# platine-crocodile.net
KiCad netlist of a schematic drawn in EAGLE
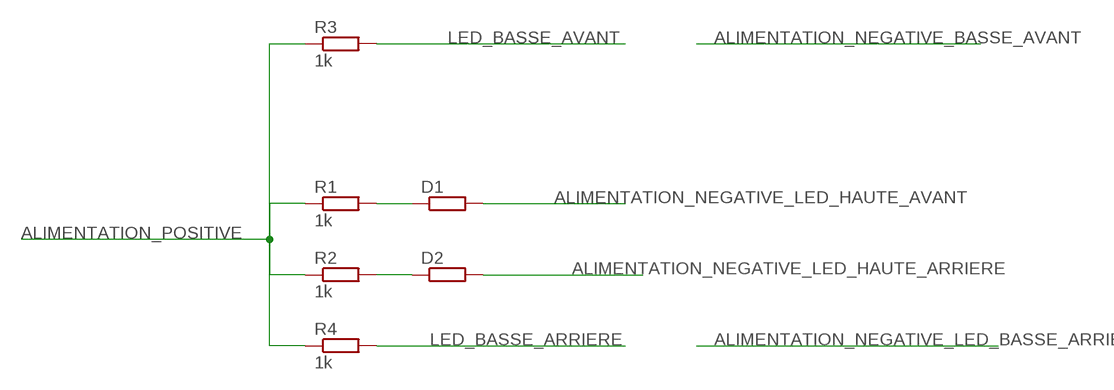
[diagram p0: schematic, sheet 1]

(export (version "E")
  (design (tool "Eeschema 10.0.6"))
  (components
    (comp (ref "D1")
      (value "R-EU_M0805")
      (footprint "eagle-import:M0805")
      (libsource (lib "eagle-import") (part "R-EU_M0805"))
    )
    (comp (ref "D2")
      (value "R-EU_M0805")
      (footprint "eagle-import:M0805")
      (libsource (lib "eagle-import") (part "R-EU_M0805"))
    )
    (comp (ref "R1")
      (value "1k")
      (footprint "eagle-import:M1206")
      (libsource (lib "eagle-import") (part "R-EU_M1206"))
    )
    (comp (ref "R2")
      (value "1k")
      (footprint "eagle-import:M1206")
      (libsource (lib "eagle-import") (part "R-EU_M1206"))
    )
    (comp (ref "R3")
      (value "1k")
      (footprint "eagle-import:M1206")
      (libsource (lib "eagle-import") (part "R-EU_M1206"))
    )
    (comp (ref "R4")
      (value "1k")
      (footprint "eagle-import:M1206")
      (libsource (lib "eagle-import") (part "R-EU_M1206"))
    )
  )
  (nets
    (net (code "3") (name "/ALIMENTATION_NEGATIVE_LED_HAUTE_ARRIERE") (class "Default")
      (node (ref "D2") (pin "2") (pinfunction "2_2") (pintype "passive"))
    )
    (net (code "4") (name "/ALIMENTATION_NEGATIVE_LED_HAUTE_AVANT") (class "Default")
      (node (ref "D1") (pin "2") (pinfunction "2_2") (pintype "passive"))
    )
    (net (code "5") (name "/ALIMENTATION_POSITIVE") (class "Default")
      (node (ref "R1") (pin "1") (pinfunction "1_1") (pintype "passive"))
      (node (ref "R2") (pin "1") (pinfunction "1_1") (pintype "passive"))
      (node (ref "R3") (pin "1") (pinfunction "1_1") (pintype "passive"))
      (node (ref "R4") (pin "1") (pinfunction "1_1") (pintype "passive"))
    )
    (net (code "6") (name "/LED_BASSE_ARRIERE") (class "Default")
      (node (ref "R4") (pin "2") (pinfunction "2_2") (pintype "passive"))
    )
    (net (code "7") (name "/LED_BASSE_AVANT") (class "Default")
      (node (ref "R3") (pin "2") (pinfunction "2_2") (pintype "passive"))
    )
    (net (code "8") (name "Net-(D1-Pad1)") (class "Default")
      (node (ref "D1") (pin "1") (pinfunction "1_1") (pintype "passive"))
      (node (ref "R1") (pin "2") (pinfunction "2_2") (pintype "passive"))
    )
    (net (code "9") (name "Net-(D2-Pad1)") (class "Default")
      (node (ref "D2") (pin "1") (pinfunction "1_1") (pintype "passive"))
      (node (ref "R2") (pin "2") (pinfunction "2_2") (pintype "passive"))
    )
  )
)
